# LedBoard.net
KiCad netlist of a schematic drawn in EAGLE
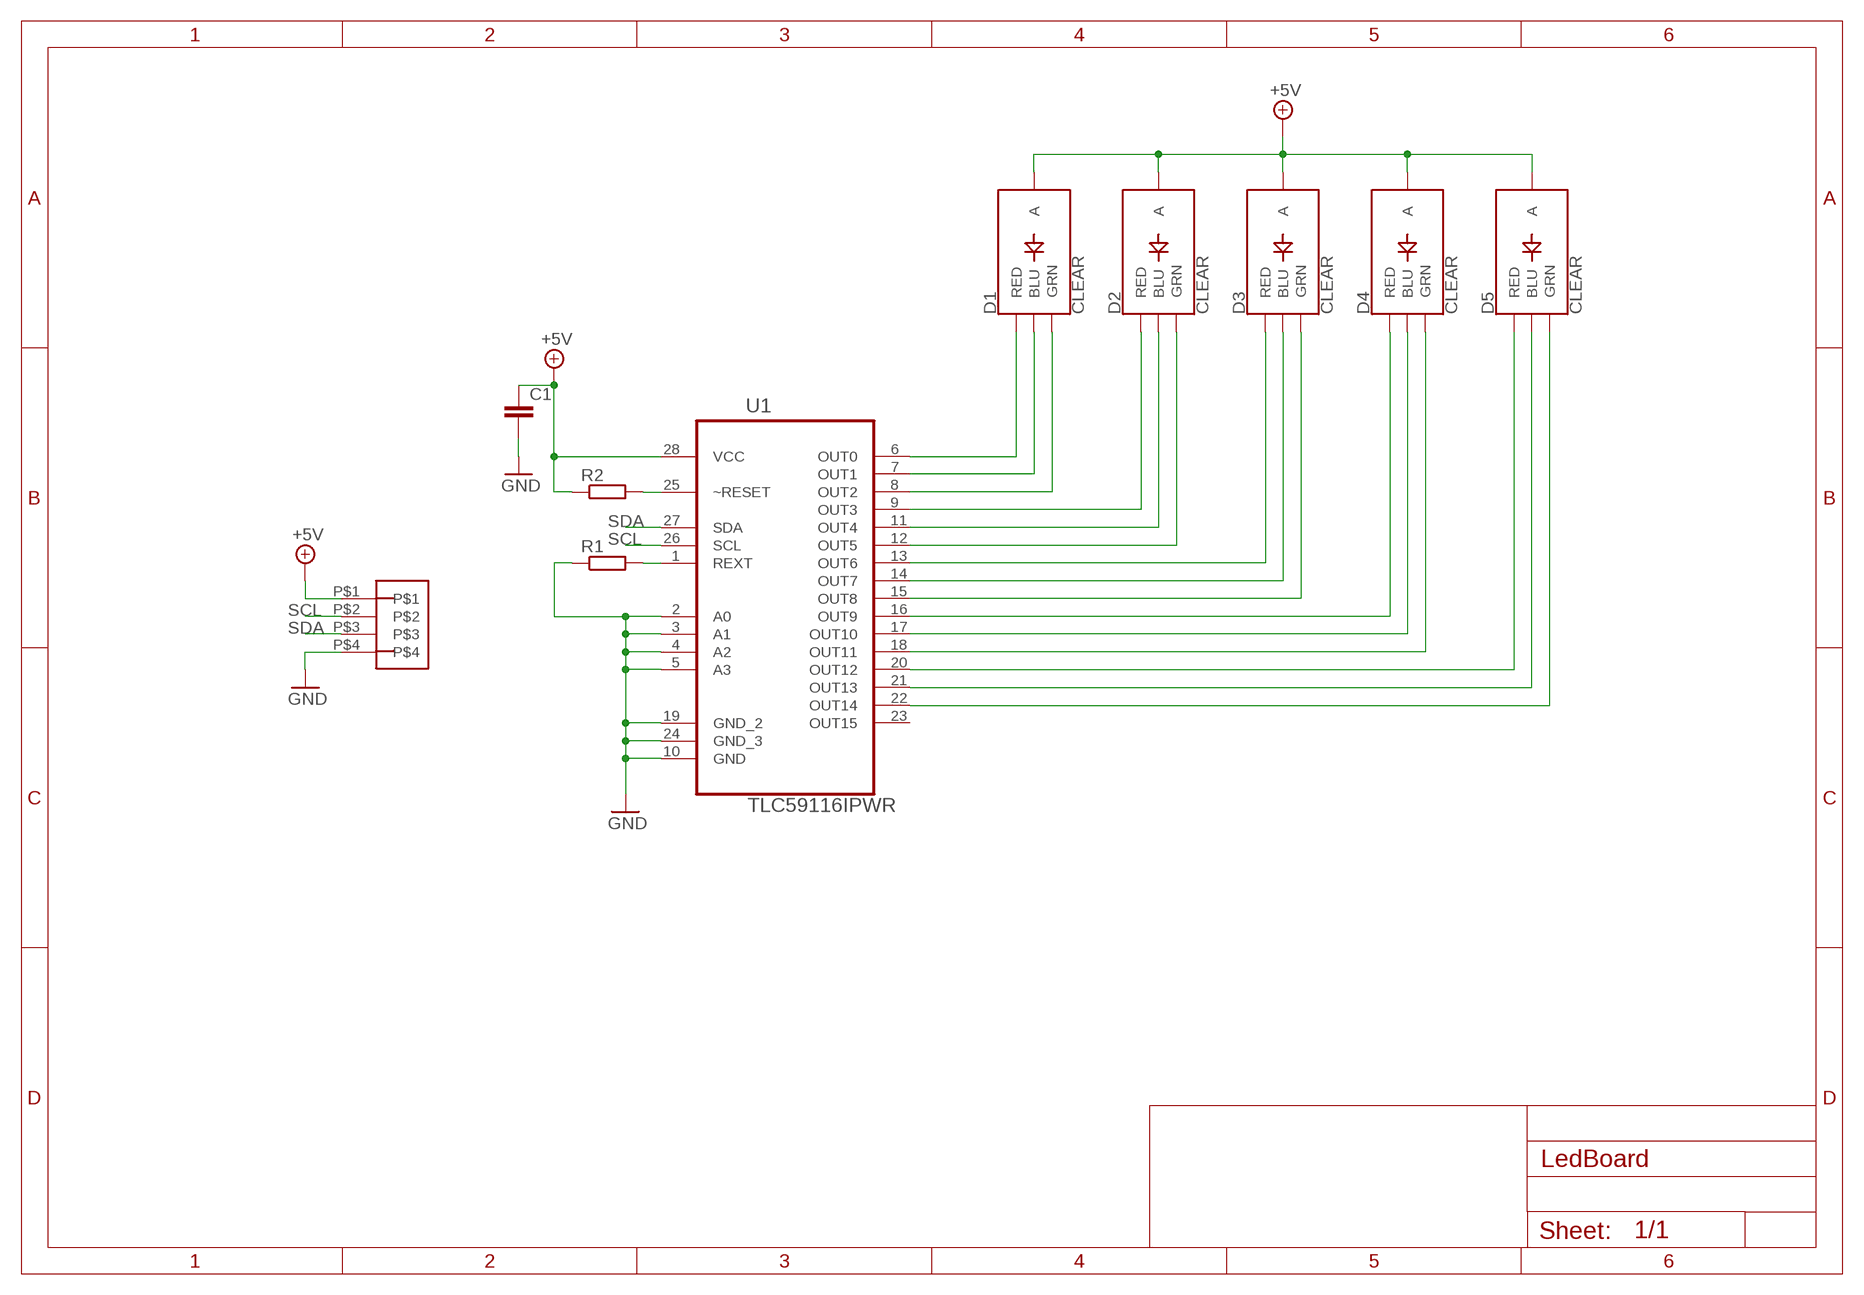
[diagram p0: schematic, sheet 1]

(export (version "E")
  (design (tool "Eeschema 10.0.6"))
  (components
    (comp (ref "C1")
      (value "C-EUC0603")
      (footprint "eagle-import:C0603")
      (libsource (lib "eagle-import") (part "C-EUC0603"))
    )
    (comp (ref "D1")
      (value "CLEAR")
      (footprint "eagle-import:LED-RGB-THRU")
      (libsource (lib "eagle-import") (part "LED-RGB-CACLEAR"))
    )
    (comp (ref "D2")
      (value "CLEAR")
      (footprint "eagle-import:LED-RGB-THRU")
      (libsource (lib "eagle-import") (part "LED-RGB-CACLEAR"))
    )
    (comp (ref "D3")
      (value "CLEAR")
      (footprint "eagle-import:LED-RGB-THRU")
      (libsource (lib "eagle-import") (part "LED-RGB-CACLEAR"))
    )
    (comp (ref "D4")
      (value "CLEAR")
      (footprint "eagle-import:LED-RGB-THRU")
      (libsource (lib "eagle-import") (part "LED-RGB-CACLEAR"))
    )
    (comp (ref "D5")
      (value "CLEAR")
      (footprint "eagle-import:LED-RGB-THRU")
      (fields (field (name "PROD_ID") "DIO-10631"))
      (libsource (lib "eagle-import") (part "LED-RGB-CACLEAR"))
    )
    (comp (ref "R1")
      (value "R-EU_R0603")
      (footprint "eagle-import:R0603")
      (libsource (lib "eagle-import") (part "R-EU_R0603"))
    )
    (comp (ref "R2")
      (value "R-EU_R0603")
      (footprint "eagle-import:R0603")
      (libsource (lib "eagle-import") (part "R-EU_R0603"))
    )
    (comp (ref "U$1")
      (value "4_PIN_JST-XH")
      (footprint "eagle-import:4_PIN_JST-XH")
      (libsource (lib "eagle-import") (part "4_PIN_JST-XH"))
    )
    (comp (ref "U1")
      (value "TLC59116IPWR")
      (footprint "eagle-import:SOP65P640X120-28N")
      (fields (field (name "MF") "Texas Instruments"))
      (libsource (lib "eagle-import") (part "TLC59116IPWR"))
    )
  )
  (nets
    (net (code "1") (name "+5V") (class "Default")
      (node (ref "C1") (pin "1") (pinfunction "1_1") (pintype "passive"))
      (node (ref "D1") (pin "2") (pinfunction "A_2") (pintype "bidirectional"))
      (node (ref "D2") (pin "2") (pinfunction "A_2") (pintype "bidirectional"))
      (node (ref "D3") (pin "2") (pinfunction "A_2") (pintype "bidirectional"))
      (node (ref "D4") (pin "2") (pinfunction "A_2") (pintype "bidirectional"))
      (node (ref "D5") (pin "2") (pinfunction "A_2") (pintype "bidirectional"))
      (node (ref "R2") (pin "1") (pinfunction "1_1") (pintype "passive"))
      (node (ref "U$1") (pin "P$1") (pinfunction "P$1_P$1") (pintype "bidirectional"))
      (node (ref "U1") (pin "28") (pinfunction "VCC_28") (pintype "power_in"))
    )
    (net (code "2") (name "/SCL") (class "Default")
      (node (ref "U$1") (pin "P$2") (pinfunction "P$2_P$2") (pintype "bidirectional"))
      (node (ref "U1") (pin "26") (pinfunction "SCL_26") (pintype "input"))
    )
    (net (code "3") (name "/SDA") (class "Default")
      (node (ref "U$1") (pin "P$3") (pinfunction "P$3_P$3") (pintype "bidirectional"))
      (node (ref "U1") (pin "27") (pinfunction "SDA_27") (pintype "bidirectional"))
    )
    (net (code "4") (name "GND") (class "Default")
      (node (ref "C1") (pin "2") (pinfunction "2_2") (pintype "passive"))
      (node (ref "R1") (pin "1") (pinfunction "1_1") (pintype "passive"))
      (node (ref "U$1") (pin "P$4") (pinfunction "P$4_P$4") (pintype "bidirectional"))
      (node (ref "U1") (pin "10") (pinfunction "GND_10") (pintype "passive"))
      (node (ref "U1") (pin "19") (pinfunction "GND_2_19") (pintype "passive"))
      (node (ref "U1") (pin "2") (pinfunction "A0_2") (pintype "input"))
      (node (ref "U1") (pin "24") (pinfunction "GND_3_24") (pintype "passive"))
      (node (ref "U1") (pin "3") (pinfunction "A1_3") (pintype "input"))
      (node (ref "U1") (pin "4") (pinfunction "A2_4") (pintype "input"))
      (node (ref "U1") (pin "5") (pinfunction "A3_5") (pintype "bidirectional"))
    )
    (net (code "5") (name "Net-(D1-BLU)") (class "Default")
      (node (ref "D1") (pin "4") (pinfunction "BLU_4") (pintype "bidirectional"))
      (node (ref "U1") (pin "7") (pinfunction "OUT1_7") (pintype "output"))
    )
    (net (code "6") (name "Net-(D1-GRN)") (class "Default")
      (node (ref "D1") (pin "3") (pinfunction "GRN_3") (pintype "bidirectional"))
      (node (ref "U1") (pin "8") (pinfunction "OUT2_8") (pintype "output"))
    )
    (net (code "7") (name "Net-(D1-RED)") (class "Default")
      (node (ref "D1") (pin "1") (pinfunction "RED_1") (pintype "bidirectional"))
      (node (ref "U1") (pin "6") (pinfunction "OUT0_6") (pintype "output"))
    )
    (net (code "8") (name "Net-(D2-BLU)") (class "Default")
      (node (ref "D2") (pin "4") (pinfunction "BLU_4") (pintype "bidirectional"))
      (node (ref "U1") (pin "11") (pinfunction "OUT4_11") (pintype "output"))
    )
    (net (code "9") (name "Net-(D2-GRN)") (class "Default")
      (node (ref "D2") (pin "3") (pinfunction "GRN_3") (pintype "bidirectional"))
      (node (ref "U1") (pin "12") (pinfunction "OUT5_12") (pintype "output"))
    )
    (net (code "10") (name "Net-(D2-RED)") (class "Default")
      (node (ref "D2") (pin "1") (pinfunction "RED_1") (pintype "bidirectional"))
      (node (ref "U1") (pin "9") (pinfunction "OUT3_9") (pintype "output"))
    )
    (net (code "11") (name "Net-(D3-BLU)") (class "Default")
      (node (ref "D3") (pin "4") (pinfunction "BLU_4") (pintype "bidirectional"))
      (node (ref "U1") (pin "14") (pinfunction "OUT7_14") (pintype "output"))
    )
    (net (code "12") (name "Net-(D3-GRN)") (class "Default")
      (node (ref "D3") (pin "3") (pinfunction "GRN_3") (pintype "bidirectional"))
      (node (ref "U1") (pin "15") (pinfunction "OUT8_15") (pintype "output"))
    )
    (net (code "13") (name "Net-(D3-RED)") (class "Default")
      (node (ref "D3") (pin "1") (pinfunction "RED_1") (pintype "bidirectional"))
      (node (ref "U1") (pin "13") (pinfunction "OUT6_13") (pintype "output"))
    )
    (net (code "14") (name "Net-(D4-BLU)") (class "Default")
      (node (ref "D4") (pin "4") (pinfunction "BLU_4") (pintype "bidirectional"))
      (node (ref "U1") (pin "17") (pinfunction "OUT10_17") (pintype "output"))
    )
    (net (code "15") (name "Net-(D4-GRN)") (class "Default")
      (node (ref "D4") (pin "3") (pinfunction "GRN_3") (pintype "bidirectional"))
      (node (ref "U1") (pin "18") (pinfunction "OUT11_18") (pintype "output"))
    )
    (net (code "16") (name "Net-(D4-RED)") (class "Default")
      (node (ref "D4") (pin "1") (pinfunction "RED_1") (pintype "bidirectional"))
      (node (ref "U1") (pin "16") (pinfunction "OUT9_16") (pintype "output"))
    )
    (net (code "17") (name "Net-(D5-BLU)") (class "Default")
      (node (ref "D5") (pin "4") (pinfunction "BLU_4") (pintype "bidirectional"))
      (node (ref "U1") (pin "21") (pinfunction "OUT13_21") (pintype "output"))
    )
    (net (code "18") (name "Net-(D5-GRN)") (class "Default")
      (node (ref "D5") (pin "3") (pinfunction "GRN_3") (pintype "bidirectional"))
      (node (ref "U1") (pin "22") (pinfunction "OUT14_22") (pintype "output"))
    )
    (net (code "19") (name "Net-(D5-RED)") (class "Default")
      (node (ref "D5") (pin "1") (pinfunction "RED_1") (pintype "bidirectional"))
      (node (ref "U1") (pin "20") (pinfunction "OUT12_20") (pintype "output"))
    )
    (net (code "20") (name "Net-(U1-REXT)") (class "Default")
      (node (ref "R1") (pin "2") (pinfunction "2_2") (pintype "passive"))
      (node (ref "U1") (pin "1") (pinfunction "REXT_1") (pintype "input"))
    )
    (net (code "21") (name "Net-(U1-~{RESET})") (class "Default")
      (node (ref "R2") (pin "2") (pinfunction "2_2") (pintype "passive"))
      (node (ref "U1") (pin "25") (pinfunction "~{RESET}_25") (pintype "input"))
    )
    (net (code "22") (name "unconnected-(U1-OUT15-Pad23)") (class "Default")
      (node (ref "U1") (pin "23") (pinfunction "OUT15_23") (pintype "output"))
    )
  )
)
